# Low-Side.net
KiCad netlist of a schematic drawn in Altium Designer
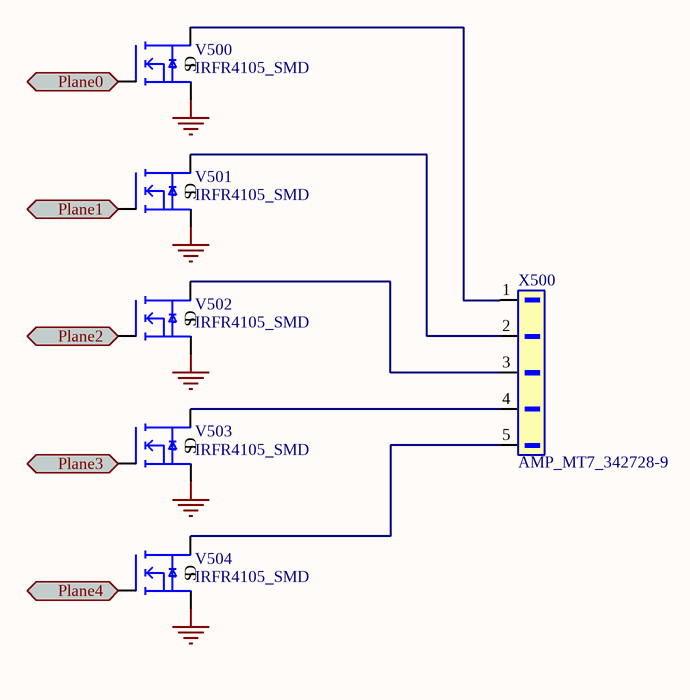
[diagram p0: Low-Side.SchDoc]

(export (version "E")
  (design (tool "Eeschema 10.0.6"))
  (components
    (comp (ref "V500")
      (value "IRFR4105_SMD")
      (footprint "DPAK_R")
      (description "IRFR4105_MOS-FET_N_SMD")
      (libsource (lib "Transistoren_SMD") (part "IRFR4105_SMD"))
    )
    (comp (ref "V501")
      (value "IRFR4105_SMD")
      (footprint "DPAK_R")
      (description "IRFR4105_MOS-FET_N_SMD")
      (libsource (lib "Transistoren_SMD") (part "IRFR4105_SMD"))
    )
    (comp (ref "V502")
      (value "IRFR4105_SMD")
      (footprint "DPAK_R")
      (description "IRFR4105_MOS-FET_N_SMD")
      (libsource (lib "Transistoren_SMD") (part "IRFR4105_SMD"))
    )
    (comp (ref "V503")
      (value "IRFR4105_SMD")
      (footprint "DPAK_R")
      (description "IRFR4105_MOS-FET_N_SMD")
      (libsource (lib "Transistoren_SMD") (part "IRFR4105_SMD"))
    )
    (comp (ref "V504")
      (value "IRFR4105_SMD")
      (footprint "DPAK_R")
      (description "IRFR4105_MOS-FET_N_SMD")
      (libsource (lib "Transistoren_SMD") (part "IRFR4105_SMD"))
    )
    (comp (ref "X500")
      (value "AMP_MT7_342728-9")
      (footprint "MT7_342728-9")
      (description "Stiftleiste_5-polig_AMP_Inkrementalgeber_stehend=MT7_342728-9")
      (libsource (lib "Stecker") (part "AMP_MT7_342728-9"))
    )
  )
  (nets
    (net (code "1") (name "/Plane0") (class "Default")
      (node (ref "V500") (pin "1") (pinfunction "G_1") (pintype "passive"))
    )
    (net (code "2") (name "/Plane1") (class "Default")
      (node (ref "V501") (pin "1") (pinfunction "G_1") (pintype "passive"))
    )
    (net (code "3") (name "/Plane2") (class "Default")
      (node (ref "V502") (pin "1") (pinfunction "G_1") (pintype "passive"))
    )
    (net (code "4") (name "/Plane3") (class "Default")
      (node (ref "V503") (pin "1") (pinfunction "G_1") (pintype "passive"))
    )
    (net (code "5") (name "/Plane4") (class "Default")
      (node (ref "V504") (pin "1") (pinfunction "G_1") (pintype "passive"))
    )
    (net (code "6") (name "GND") (class "Default")
      (node (ref "V500") (pin "3") (pinfunction "S_3") (pintype "passive"))
      (node (ref "V501") (pin "3") (pinfunction "S_3") (pintype "passive"))
      (node (ref "V502") (pin "3") (pinfunction "S_3") (pintype "passive"))
      (node (ref "V503") (pin "3") (pinfunction "S_3") (pintype "passive"))
      (node (ref "V504") (pin "3") (pinfunction "S_3") (pintype "passive"))
    )
    (net (code "7") (name "Net-(V500-D)") (class "Default")
      (node (ref "V500") (pin "2") (pinfunction "D_2") (pintype "passive"))
      (node (ref "X500") (pin "1") (pintype "passive"))
    )
    (net (code "8") (name "Net-(V501-D)") (class "Default")
      (node (ref "V501") (pin "2") (pinfunction "D_2") (pintype "passive"))
      (node (ref "X500") (pin "2") (pintype "passive"))
    )
    (net (code "9") (name "Net-(V502-D)") (class "Default")
      (node (ref "V502") (pin "2") (pinfunction "D_2") (pintype "passive"))
      (node (ref "X500") (pin "3") (pintype "passive"))
    )
    (net (code "10") (name "Net-(V503-D)") (class "Default")
      (node (ref "V503") (pin "2") (pinfunction "D_2") (pintype "passive"))
      (node (ref "X500") (pin "4") (pintype "passive"))
    )
    (net (code "11") (name "Net-(V504-D)") (class "Default")
      (node (ref "V504") (pin "2") (pinfunction "D_2") (pintype "passive"))
      (node (ref "X500") (pin "5") (pintype "passive"))
    )
  )
)
